# Sheet1.net
KiCad netlist of a schematic drawn in Altium Designer
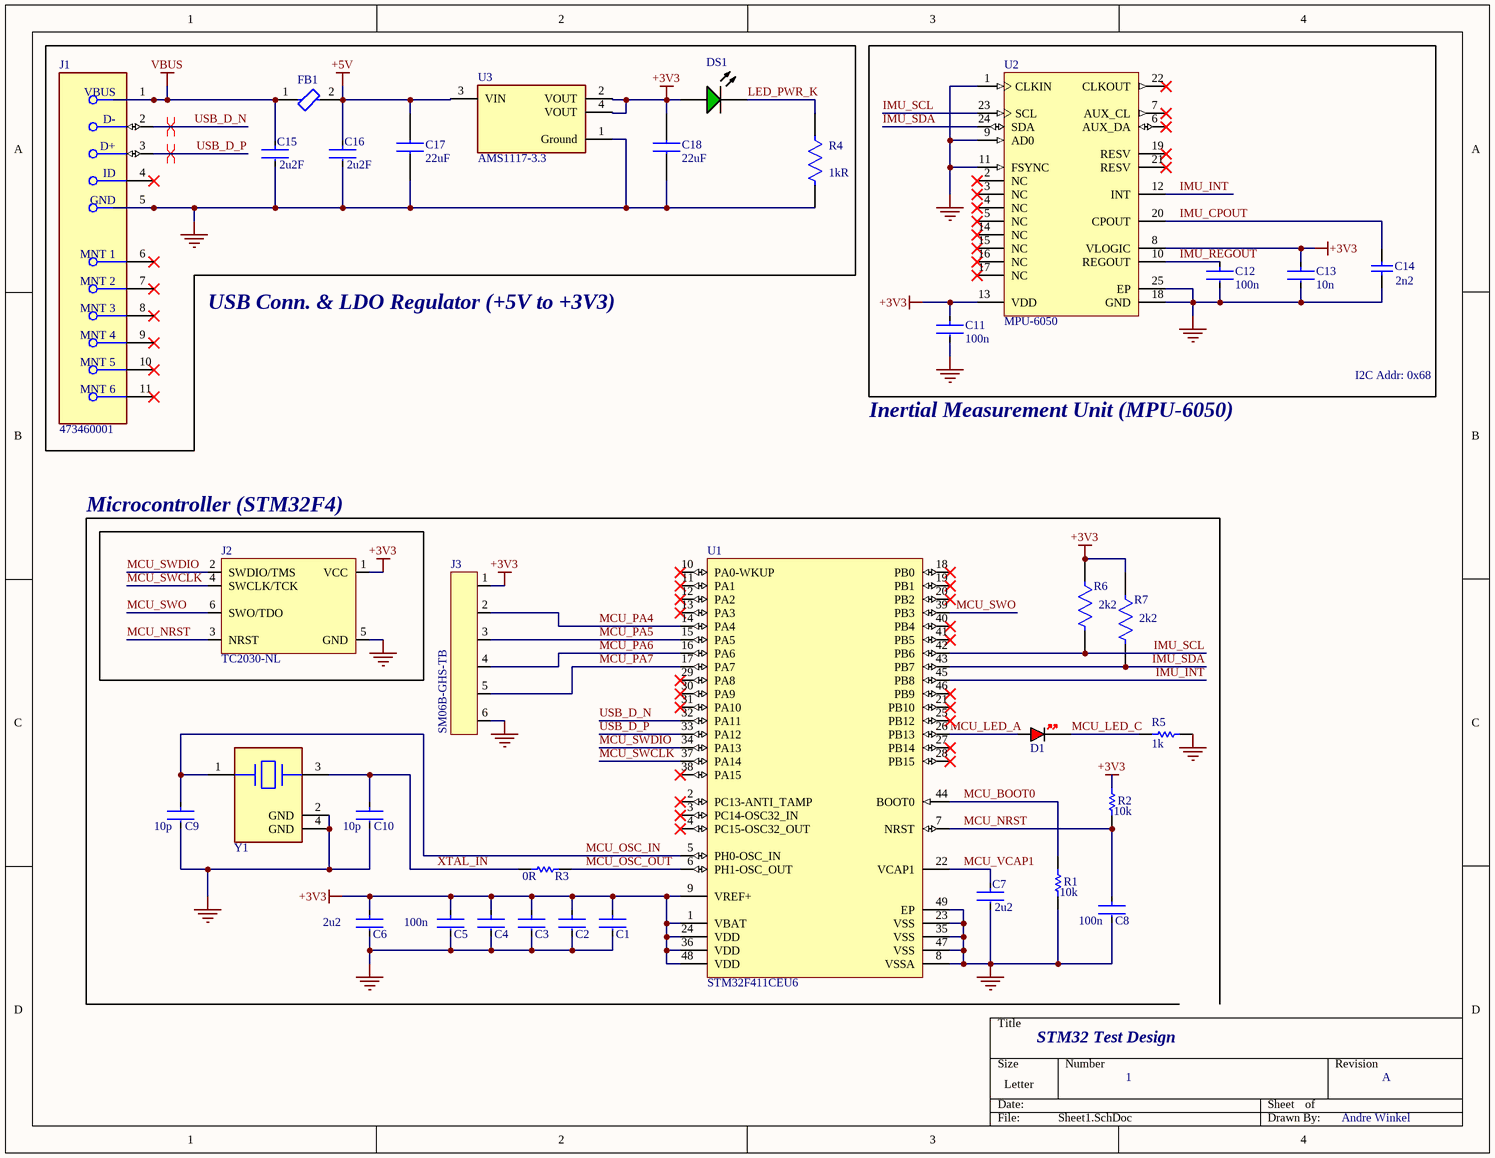
[diagram p0: Sheet1.SchDoc]

(export (version "E")
  (design (tool "Eeschema 10.0.6"))
  (components
    (comp (ref "C1")
      (value "GCM155R71C104KA55D")
      (footprint "FP-GCM155-0_05-IPC_C")
      (description "Ceramic Capacitor for Automotive 100nF ±10% 16VDC X7R 0402 Paper T/R")
      (fields (field (name "VOLTAGE") "16V") (field (name "TOLERANCE") "10%"))
      (libsource (lib "Altium Content Vault") (part "02cd4be3c70576c341d710602a673aa"))
    )
    (comp (ref "C2")
      (value "GCM155R71C104KA55D")
      (footprint "FP-GCM155-0_05-IPC_C")
      (description "Ceramic Capacitor for Automotive 100nF ±10% 16VDC X7R 0402 Paper T/R")
      (fields (field (name "VOLTAGE") "16V") (field (name "TOLERANCE") "10%"))
      (libsource (lib "Altium Content Vault") (part "02cd4be3c70576c341d710602a673aa"))
    )
    (comp (ref "C3")
      (value "GCM155R71C104KA55D")
      (footprint "FP-GCM155-0_05-IPC_C")
      (description "Ceramic Capacitor for Automotive 100nF ±10% 16VDC X7R 0402 Paper T/R")
      (fields (field (name "VOLTAGE") "16V") (field (name "TOLERANCE") "10%"))
      (libsource (lib "Altium Content Vault") (part "02cd4be3c70576c341d710602a673aa"))
    )
    (comp (ref "C4")
      (value "GCM155R71C104KA55D")
      (footprint "FP-GCM155-0_05-IPC_C")
      (description "Ceramic Capacitor for Automotive 100nF ±10% 16VDC X7R 0402 Paper T/R")
      (fields (field (name "VOLTAGE") "16V") (field (name "TOLERANCE") "10%"))
      (libsource (lib "Altium Content Vault") (part "02cd4be3c70576c341d710602a673aa"))
    )
    (comp (ref "C5")
      (value "GCM155R71C104KA55D")
      (footprint "FP-GCM155-0_05-IPC_C")
      (description "Ceramic Capacitor for Automotive 100nF ±10% 16VDC X7R 0402 Paper T/R")
      (fields
        (field (name "VOLTAGE") "16V")
        (field (name "TOLERANCE") "10%")
        (field (name "CAPACITANCE") "100n")
      )
      (libsource (lib "Altium Content Vault") (part "02cd4be3c70576c341d710602a673aa"))
    )
    (comp (ref "C6")
      (value "CGA3E1X7S1C225K080AE")
      (footprint "FP-CGA3E-0_3-0_1-IPC_C")
      (description "Cap Ceramic 2.2uF 16V X7S 10% Pad SMD 0603 +125°C Automotive T/R")
      (fields (field (name "TOLERANCE") "10%") (field (name "CAPACITANCE") "2u2"))
      (libsource (lib "Altium Content Vault") (part "b4654b650e69147ec39a6b967a45e02"))
    )
    (comp (ref "C7")
      (value "CGA3E1X7S1C225K080AE")
      (footprint "FP-CGA3E-0_3-0_1-IPC_C")
      (description "Cap Ceramic 2.2uF 16V X7S 10% Pad SMD 0603 +125°C Automotive T/R")
      (fields (field (name "TOLERANCE") "10%") (field (name "CAPACITANCE") "2u2"))
      (libsource (lib "Altium Content Vault") (part "b4654b650e69147ec39a6b967a45e02"))
    )
    (comp (ref "C8")
      (value "GCM155R71C104KA55D")
      (footprint "FP-GCM155-0_05-IPC_C")
      (description "Ceramic Capacitor for Automotive 100nF ±10% 16VDC X7R 0402 Paper T/R")
      (fields
        (field (name "VOLTAGE") "16V")
        (field (name "TOLERANCE") "10%")
        (field (name "CAPACITANCE") "100n")
      )
      (libsource (lib "Altium Content Vault") (part "02cd4be3c70576c341d710602a673aa"))
    )
    (comp (ref "C9")
      (value "GJM0335C1E100GB01D")
      (footprint "FP-GJM033-0_03-IPC_B")
      (description "Ceramic Capacitor 10pF ±2% 25V C0G 0201 (0603 Metric)")
      (fields (field (name "CAPACITANCE") "10p") (field (name "TOLERANCE") "2%"))
      (libsource (lib "Altium Content Vault") (part "b4654b650e69147ec39a6b967a45e02"))
    )
    (comp (ref "C10")
      (value "GJM0335C1E100GB01D")
      (footprint "FP-GJM033-0_03-IPC_B")
      (description "Ceramic Capacitor 10pF ±2% 25V C0G 0201 (0603 Metric)")
      (fields (field (name "CAPACITANCE") "10p") (field (name "TOLERANCE") "2%"))
      (libsource (lib "Altium Content Vault") (part "b4654b650e69147ec39a6b967a45e02"))
    )
    (comp (ref "C11")
      (value "GCM155R71C104KA55D")
      (footprint "FP-GCM155-0_05-IPC_C")
      (description "Ceramic Capacitor for Automotive 100nF ±10% 16VDC X7R 0402 Paper T/R")
      (fields
        (field (name "VOLTAGE") "16V")
        (field (name "TOLERANCE") "10%")
        (field (name "CAPACITANCE") "100n")
      )
      (libsource (lib "Altium Content Vault") (part "02cd4be3c70576c341d710602a673aa"))
    )
    (comp (ref "C12")
      (value "GCM155R71C104KA55D")
      (footprint "FP-GCM155-0_05-IPC_C")
      (description "Ceramic Capacitor for Automotive 100nF ±10% 16VDC X7R 0402 Paper T/R")
      (fields
        (field (name "VOLTAGE") "16V")
        (field (name "TOLERANCE") "10%")
        (field (name "CAPACITANCE") "100n")
      )
      (libsource (lib "Altium Content Vault") (part "02cd4be3c70576c341d710602a673aa"))
    )
    (comp (ref "C13")
      (value "C0603X7R0J103K030BA")
      (footprint "FP-C0603-030-0_03-IPC_B")
      (description "Multilayer Ceramic Capacitors 10nF ±10% 6.3V X7R SMD 0201")
      (fields (field (name "CAPACITANCE") "10n") (field (name "TOLERANCE") "10%"))
      (libsource (lib "Altium Content Vault") (part "02cd4be3c70576c341d710602a673aa"))
    )
    (comp (ref "C14")
      (value "2n2")
      (footprint "CAPC1608X87X35NL15T15")
      (fields (field (name "MANUFACTURER") "Kemet") (field (name "PART NUMBER") "C0603X222K5RACTU"))
      (libsource (lib "Altium Content Vault") (part "CAP"))
    )
    (comp (ref "C15")
      (value "CGA3E1X7S1C225K080AE")
      (footprint "FP-CGA3E-0_3-0_1-IPC_C")
      (description "Cap Ceramic 2.2uF 16V X7S 10% Pad SMD 0603 +125°C Automotive T/R")
      (fields (field (name "TOLERANCE") "10%") (field (name "CAPACITANCE") "2u2F"))
      (libsource (lib "Altium Content Vault") (part "b4654b650e69147ec39a6b967a45e02"))
    )
    (comp (ref "C16")
      (value "CGA3E1X7S1C225K080AE")
      (footprint "FP-CGA3E-0_3-0_1-IPC_C")
      (description "Cap Ceramic 2.2uF 16V X7S 10% Pad SMD 0603 +125°C Automotive T/R")
      (fields (field (name "TOLERANCE") "10%") (field (name "CAPACITANCE") "2u2F"))
      (libsource (lib "Altium Content Vault") (part "b4654b650e69147ec39a6b967a45e02"))
    )
    (comp (ref "C17")
      (value "C2012X5R1C226M085AC")
      (footprint "SamacSys:C2012_Commercial")
      (description "Capacitor")
      (fields (field (name "MOUSER PART NUMBER") "810-C2012X5R1C226MAC") (field (name "CAPACITANCE") "22uF"))
      (libsource (lib "*") (part "C2012X5R1C226M085AC"))
    )
    (comp (ref "C18")
      (value "C2012X5R1C226M085AC")
      (footprint "SamacSys:C2012_Commercial")
      (description "Capacitor")
      (fields (field (name "MOUSER PART NUMBER") "810-C2012X5R1C226MAC") (field (name "CAPACITANCE") "22uF"))
      (libsource (lib "*") (part "C2012X5R1C226M085AC"))
    )
    (comp (ref "D1")
      (value "RED")
      (footprint "LED_0402_RED")
      (description "LED 0402 RED SMD")
      (libsource (lib "Schematic-Lib-PhilsLab") (part "LED_0402_RED"))
    )
    (comp (ref "DS1")
      (value "HSMG-C170")
      (footprint "AVAG-HSMX-C170_V")
      (description "Chip LED, Green, 2.2 V, -40 to 85 degC, 2-Pin SMD, Pb-Free, Tape and Reel")
      (fields (field (name "MANUFACTURER") "Avago"))
      (libsource (lib "Altium Content Vault") (part "LED_GREEN_A1K2-2"))
    )
    (comp (ref "FB1")
      (value "BLM31PG121SN1L")
      (footprint "FP-BLM31-0_2-t1_1-MFG")
      (description "Chip Ferrite Bead Array, 1206, 120Ω @ 100MHz, 0.02Ω, 25%, 3.5A")
      (fields (field (name "TOLERANCE") "25%"))
      (libsource (lib "Altium Content Vault") (part "5f30dd21d616792df468990f7003faa"))
    )
    (comp (ref "J1")
      (value "473460001")
      (footprint "FP-473460001-MFG")
      (description "CONN RCPT USB2.0 MICRO B SMD R/A")
      (fields
        (field (name "OCTOPART") "https://octopart.com/47346-0001-molex-7164928")
        (field (name "MANUFACTURER") "Molex")
      )
      (libsource (lib "Altium Content Vault") (part "53ae1f1d9b557310b43ca686e5bb76a"))
    )
    (comp (ref "J2")
      (value "TC2030-NL")
      (footprint "TC2030-NL-FP")
      (description "Tag-Connect No-Solder SWD Debug Connector (No Legs) DO NOT PLACE")
      (fields
        (field (name "MANUFACTURER") "Tag-Connect")
        (field (name "MANUFACTURER PART NUMBER") "TC2030-NL-FP")
      )
      (libsource (lib "Schematic-Lib-PhilsLab") (part "TC2030-NL"))
    )
    (comp (ref "J3")
      (value "SM06B-GHS-TB")
      (footprint "SM06B-GHS-TB")
      (description "Header Connector 6 Position 1.25MM Pitch SMD Horizontal JST GH")
      (fields (field (name "MANUFACTURER") "JST"))
      (libsource (lib "Schematic-Lib-PhilsLab") (part "SM06B-GHS-TB"))
    )
    (comp (ref "R1")
      (value "CRG0201F10K")
      (footprint "RESC0603X26X15LL03T05")
      (fields (field (name "MANUFACTURER") "TE Connectivity / AMP") (field (name "RESISTANCE") "10k"))
      (libsource (lib "Altium Content Vault") (part "RES"))
    )
    (comp (ref "R2")
      (value "CRG0201F10K")
      (footprint "RESC0603X26X15LL03T05")
      (fields (field (name "MANUFACTURER") "TE Connectivity / AMP") (field (name "RESISTANCE") "10k"))
      (libsource (lib "Altium Content Vault") (part "RES"))
    )
    (comp (ref "R3")
      (value "ERJ2GE0R00X")
      (footprint "RESC1005X40X25LL05T05")
      (description "Chip Resistor, 0 Ohm, 0.1 W, -55 to 155 degC, 0402 (1005 Metric), RoHS, Tape and Reel")
      (fields
        (field (name "MANUFACTURER") "Panasonic")
        (field (name "RESISTANCE") "0R")
        (field (name "TOLERANCE") "5%")
      )
      (libsource (lib "Altium Content Vault") (part "RES-2"))
    )
    (comp (ref "R4")
      (value "AC0603FR-071KL")
      (footprint "FP-AC0603-IPC_B")
      (description "RES 1kΩ 1.00% 0.1W 0603")
      (fields (field (name "TOLERANCE") "1%") (field (name "RESISTANCE") "1kR"))
      (libsource (lib "Altium Content Vault") (part "1029c3af85768c4190bb7ad29bc67b5"))
    )
    (comp (ref "R5")
      (value "CRG0201F10K")
      (footprint "RESC0603X26X15LL03T05")
      (fields (field (name "MANUFACTURER") "TE Connectivity / AMP") (field (name "RESISTANCE") "1k"))
      (libsource (lib "Altium Content Vault") (part "RES"))
    )
    (comp (ref "R6")
      (value "2k2")
      (footprint "FP-CRGCQ0402-IPC_C")
      (description "CRGCQ0402 2.2KΩ 5% ±100ppm/°C 50V")
      (fields
        (field (name "MANUFACTURER") "TE Connectivity")
        (field (name "MANUFACTURER PART NUMBER") "CRGCQ0402J2K2")
      )
      (libsource (lib "Altium Content Vault") (part "1029c3af85768c4190bb7ad29bc67b5"))
    )
    (comp (ref "R7")
      (value "2k2")
      (footprint "FP-CRGCQ0402-IPC_C")
      (description "CRGCQ0402 2.2KΩ 5% ±100ppm/°C 50V")
      (fields
        (field (name "MANUFACTURER") "TE Connectivity")
        (field (name "MANUFACTURER PART NUMBER") "CRGCQ0402J2K2")
      )
      (libsource (lib "Altium Content Vault") (part "1029c3af85768c4190bb7ad29bc67b5"))
    )
    (comp (ref "U1")
      (value "STM32F411CEU6")
      (footprint "STM-UFQFPN48_L")
      (libsource (lib "Altium Content Vault") (part "MC-ARM-STM32F411-UFQFPN48"))
    )
    (comp (ref "U2")
      (value "MPU-6050")
      (footprint "IS-QFN-24_V")
      (fields (field (name "MANUFACTURER") "InvenSense"))
      (libsource (lib "Altium Content Vault") (part "IS-MPU-6050-QFN-24"))
    )
    (comp (ref "U3")
      (value "AMS1117-3.3")
      (footprint "FP-AMS1117-IPC_C")
      (description "LDO Voltage Regulators 1A, 3.3V")
      (fields
        (field (name "OCTOPART") "https://octopart.com/ams1117-3.3-advanced+monolithic+systems-25899300")
        (field (name "MANUFACTURER") "Advanced Monolithic Systems")
      )
      (libsource (lib "Altium Content Vault") (part "8bdbb5f8e77002000e30dd2845d0354"))
    )
    (comp (ref "Y1")
      (value "ABM10AIG-24.000MHZ-2Z-T")
      (footprint "FP-ABM10AIG-MFG")
      (description "Crystal 24MHz ±20ppm 10pF SMD-4 2.5mm x 2mm Automotive")
      (libsource (lib "Altium Content Vault") (part "40c3c19da1ce8e2d75e34138d1085e7"))
    )
  )
  (nets
    (net (code "1") (name "+3V3") (class "Default")
      (node (ref "C1") (pin "1") (pinfunction "1_1") (pintype "passive"))
      (node (ref "C11") (pin "1") (pinfunction "1_1") (pintype "passive"))
      (node (ref "C13") (pin "1") (pinfunction "1_1") (pintype "passive"))
      (node (ref "C18") (pin "1") (pinfunction "1_1") (pintype "passive"))
      (node (ref "C2") (pin "1") (pinfunction "1_1") (pintype "passive"))
      (node (ref "C3") (pin "1") (pinfunction "1_1") (pintype "passive"))
      (node (ref "C4") (pin "1") (pinfunction "1_1") (pintype "passive"))
      (node (ref "C5") (pin "1") (pinfunction "1_1") (pintype "passive"))
      (node (ref "C6") (pin "1") (pinfunction "1_1") (pintype "passive"))
      (node (ref "DS1") (pin "1") (pinfunction "A_1") (pintype "passive"))
      (node (ref "J2") (pin "1") (pinfunction "VCC_1") (pintype "passive"))
      (node (ref "J3") (pin "1") (pinfunction "1_1") (pintype "passive"))
      (node (ref "R2") (pin "2") (pinfunction "2_2") (pintype "passive"))
      (node (ref "R6") (pin "1") (pinfunction "1_1") (pintype "passive"))
      (node (ref "R7") (pin "1") (pinfunction "1_1") (pintype "passive"))
      (node (ref "U1") (pin "1") (pinfunction "VBAT_1") (pintype "power_in"))
      (node (ref "U1") (pin "24") (pinfunction "VDD_24") (pintype "power_in"))
      (node (ref "U1") (pin "36") (pinfunction "VDD_36") (pintype "power_in"))
      (node (ref "U1") (pin "48") (pinfunction "VDD_48") (pintype "power_in"))
      (node (ref "U1") (pin "9") (pinfunction "VREF+_9") (pintype "power_in"))
      (node (ref "U2") (pin "13") (pinfunction "VDD_13") (pintype "power_in"))
      (node (ref "U2") (pin "8") (pinfunction "VLOGIC_8") (pintype "power_in"))
      (node (ref "U3") (pin "2") (pinfunction "VOUT_2") (pintype "passive"))
      (node (ref "U3") (pin "4") (pinfunction "VOUT_4") (pintype "passive"))
    )
    (net (code "2") (name "+5V") (class "Default")
      (node (ref "C16") (pin "1") (pinfunction "1_1") (pintype "passive"))
      (node (ref "C17") (pin "1") (pinfunction "1_1") (pintype "passive"))
      (node (ref "FB1") (pin "2") (pinfunction "2_2") (pintype "passive"))
      (node (ref "U3") (pin "3") (pinfunction "VIN_3") (pintype "power_in"))
    )
    (net (code "3") (name "/IMU_CPOUT") (class "Default")
      (node (ref "C14") (pin "1") (pinfunction "1_1") (pintype "passive"))
      (node (ref "U2") (pin "20") (pinfunction "CPOUT_20") (pintype "passive"))
    )
    (net (code "4") (name "/IMU_INT") (class "Default")
      (node (ref "U1") (pin "45") (pinfunction "PB8_45") (pintype "bidirectional"))
      (node (ref "U2") (pin "12") (pinfunction "INT_12") (pintype "open_collector"))
    )
    (net (code "5") (name "/IMU_REGOUT") (class "Default")
      (node (ref "C12") (pin "1") (pinfunction "1_1") (pintype "passive"))
      (node (ref "U2") (pin "10") (pinfunction "REGOUT_10") (pintype "passive"))
    )
    (net (code "6") (name "/IMU_SCL") (class "Default")
      (node (ref "R6") (pin "2") (pinfunction "2_2") (pintype "passive"))
      (node (ref "U1") (pin "42") (pinfunction "PB6_42") (pintype "bidirectional"))
      (node (ref "U2") (pin "23") (pinfunction "SCL_23") (pintype "input"))
    )
    (net (code "7") (name "/IMU_SDA") (class "Default")
      (node (ref "R7") (pin "2") (pinfunction "2_2") (pintype "passive"))
      (node (ref "U1") (pin "43") (pinfunction "PB7_43") (pintype "bidirectional"))
      (node (ref "U2") (pin "24") (pinfunction "SDA_24") (pintype "bidirectional"))
    )
    (net (code "8") (name "/LED_PWR_K") (class "Default")
      (node (ref "DS1") (pin "2") (pinfunction "K_2") (pintype "passive"))
      (node (ref "R4") (pin "1") (pinfunction "1_1") (pintype "passive"))
    )
    (net (code "9") (name "/MCU_BOOT0") (class "Default")
      (node (ref "R1") (pin "2") (pinfunction "2_2") (pintype "passive"))
      (node (ref "U1") (pin "44") (pinfunction "BOOT0_44") (pintype "input"))
    )
    (net (code "10") (name "/MCU_LED_A") (class "Default")
      (node (ref "D1") (pin "A") (pinfunction "A_A") (pintype "passive"))
      (node (ref "U1") (pin "26") (pinfunction "PB13_26") (pintype "bidirectional"))
    )
    (net (code "11") (name "/MCU_LED_C") (class "Default")
      (node (ref "D1") (pin "K") (pinfunction "K_K") (pintype "passive"))
      (node (ref "R5") (pin "2") (pinfunction "2_2") (pintype "passive"))
    )
    (net (code "12") (name "/MCU_NRST") (class "Default")
      (node (ref "C8") (pin "1") (pinfunction "1_1") (pintype "passive"))
      (node (ref "J2") (pin "3") (pinfunction "NRST_3") (pintype "passive"))
      (node (ref "R2") (pin "1") (pinfunction "1_1") (pintype "passive"))
      (node (ref "U1") (pin "7") (pinfunction "NRST_7") (pintype "bidirectional"))
    )
    (net (code "13") (name "/MCU_OSC_IN") (class "Default")
      (node (ref "C9") (pin "1") (pinfunction "1_1") (pintype "passive"))
      (node (ref "U1") (pin "5") (pinfunction "PH0-OSC_IN_5") (pintype "bidirectional"))
      (node (ref "Y1") (pin "1") (pinfunction "1_Crystal_1") (pintype "passive"))
    )
    (net (code "14") (name "/MCU_OSC_OUT") (class "Default")
      (node (ref "R3") (pin "2") (pinfunction "2_2") (pintype "passive"))
      (node (ref "U1") (pin "6") (pinfunction "PH1-OSC_OUT_6") (pintype "bidirectional"))
    )
    (net (code "15") (name "/MCU_PA4") (class "Default")
      (node (ref "J3") (pin "2") (pinfunction "2_2") (pintype "passive"))
      (node (ref "U1") (pin "14") (pinfunction "PA4_14") (pintype "bidirectional"))
    )
    (net (code "16") (name "/MCU_PA5") (class "Default")
      (node (ref "J3") (pin "3") (pinfunction "3_3") (pintype "passive"))
      (node (ref "U1") (pin "15") (pinfunction "PA5_15") (pintype "bidirectional"))
    )
    (net (code "17") (name "/MCU_PA6") (class "Default")
      (node (ref "J3") (pin "4") (pinfunction "4_4") (pintype "passive"))
      (node (ref "U1") (pin "16") (pinfunction "PA6_16") (pintype "bidirectional"))
    )
    (net (code "18") (name "/MCU_PA7") (class "Default")
      (node (ref "J3") (pin "5") (pinfunction "5_5") (pintype "passive"))
      (node (ref "U1") (pin "17") (pinfunction "PA7_17") (pintype "bidirectional"))
    )
    (net (code "19") (name "/MCU_SWCLK") (class "Default")
      (node (ref "J2") (pin "4") (pinfunction "SWCLK/TCK_4") (pintype "passive"))
      (node (ref "U1") (pin "37") (pinfunction "PA14_37") (pintype "bidirectional"))
    )
    (net (code "20") (name "/MCU_SWDIO") (class "Default")
      (node (ref "J2") (pin "2") (pinfunction "SWDIO/TMS_2") (pintype "passive"))
      (node (ref "U1") (pin "34") (pinfunction "PA13_34") (pintype "bidirectional"))
    )
    (net (code "21") (name "/MCU_SWO") (class "Default")
      (node (ref "J2") (pin "6") (pinfunction "SWO/TDO_6") (pintype "passive"))
      (node (ref "U1") (pin "39") (pinfunction "PB3_39") (pintype "bidirectional"))
    )
    (net (code "22") (name "/MCU_VCAP1") (class "Default")
      (node (ref "C7") (pin "1") (pinfunction "1_1") (pintype "passive"))
      (node (ref "U1") (pin "22") (pinfunction "VCAP1_22") (pintype "passive"))
    )
    (net (code "23") (name "/USB_D_N") (class "Default")
      (node (ref "J1") (pin "2") (pinfunction "D-_2") (pintype "bidirectional"))
      (node (ref "U1") (pin "32") (pinfunction "PA11_32") (pintype "bidirectional"))
    )
    (net (code "24") (name "/USB_D_P") (class "Default")
      (node (ref "J1") (pin "3") (pinfunction "D+_3") (pintype "bidirectional"))
      (node (ref "U1") (pin "33") (pinfunction "PA12_33") (pintype "bidirectional"))
    )
    (net (code "25") (name "/XTAL_IN") (class "Default")
      (node (ref "C10") (pin "1") (pinfunction "1_1") (pintype "passive"))
      (node (ref "R3") (pin "1") (pinfunction "1_1") (pintype "passive"))
      (node (ref "Y1") (pin "3") (pinfunction "2_Crystal_3") (pintype "passive"))
    )
    (net (code "26") (name "GND") (class "Default")
      (node (ref "C1") (pin "2") (pinfunction "2_2") (pintype "passive"))
      (node (ref "C10") (pin "2") (pinfunction "2_2") (pintype "passive"))
      (node (ref "C11") (pin "2") (pinfunction "2_2") (pintype "passive"))
      (node (ref "C12") (pin "2") (pinfunction "2_2") (pintype "passive"))
      (node (ref "C13") (pin "2") (pinfunction "2_2") (pintype "passive"))
      (node (ref "C14") (pin "2") (pinfunction "2_2") (pintype "passive"))
      (node (ref "C15") (pin "2") (pinfunction "2_2") (pintype "passive"))
      (node (ref "C16") (pin "2") (pinfunction "2_2") (pintype "passive"))
      (node (ref "C17") (pin "2") (pinfunction "2_2") (pintype "passive"))
      (node (ref "C18") (pin "2") (pinfunction "2_2") (pintype "passive"))
      (node (ref "C2") (pin "2") (pinfunction "2_2") (pintype "passive"))
      (node (ref "C3") (pin "2") (pinfunction "2_2") (pintype "passive"))
      (node (ref "C4") (pin "2") (pinfunction "2_2") (pintype "passive"))
      (node (ref "C5") (pin "2") (pinfunction "2_2") (pintype "passive"))
      (node (ref "C6") (pin "2") (pinfunction "2_2") (pintype "passive"))
      (node (ref "C7") (pin "2") (pinfunction "2_2") (pintype "passive"))
      (node (ref "C8") (pin "2") (pinfunction "2_2") (pintype "passive"))
      (node (ref "C9") (pin "2") (pinfunction "2_2") (pintype "passive"))
      (node (ref "J1") (pin "5") (pinfunction "GND_5") (pintype "power_in"))
      (node (ref "J2") (pin "5") (pinfunction "GND_5") (pintype "passive"))
      (node (ref "J3") (pin "6") (pinfunction "6_6") (pintype "passive"))
      (node (ref "R1") (pin "1") (pinfunction "1_1") (pintype "passive"))
      (node (ref "R4") (pin "2") (pinfunction "2_2") (pintype "passive"))
      (node (ref "R5") (pin "1") (pinfunction "1_1") (pintype "passive"))
      (node (ref "U1") (pin "23") (pinfunction "VSS_23") (pintype "power_in"))
      (node (ref "U1") (pin "35") (pinfunction "VSS_35") (pintype "power_in"))
      (node (ref "U1") (pin "47") (pinfunction "VSS_47") (pintype "power_in"))
      (node (ref "U1") (pin "49") (pinfunction "EP_49") (pintype "power_in"))
      (node (ref "U1") (pin "8") (pinfunction "VSSA_8") (pintype "power_in"))
      (node (ref "U2") (pin "1") (pinfunction "CLKIN_1") (pintype "input"))
      (node (ref "U2") (pin "11") (pinfunction "FSYNC_11") (pintype "input"))
      (node (ref "U2") (pin "18") (pinfunction "GND_18") (pintype "power_in"))
      (node (ref "U2") (pin "25") (pinfunction "EP_25") (pintype "power_in"))
      (node (ref "U2") (pin "9") (pinfunction "AD0_9") (pintype "input"))
      (node (ref "U3") (pin "1") (pinfunction "Ground_1") (pintype "power_in"))
      (node (ref "Y1") (pin "2") (pinfunction "GND_2") (pintype "power_in"))
      (node (ref "Y1") (pin "4") (pinfunction "GND_4") (pintype "power_in"))
    )
    (net (code "27") (name "VBUS") (class "Default")
      (node (ref "C15") (pin "1") (pinfunction "1_1") (pintype "passive"))
      (node (ref "FB1") (pin "1") (pinfunction "1_1") (pintype "passive"))
      (node (ref "J1") (pin "1") (pinfunction "VBUS_1") (pintype "power_in"))
    )
    (net (code "28") (name "unconnected-(J1-ID-Pad4)") (class "Default")
      (node (ref "J1") (pin "4") (pinfunction "ID_4") (pintype "passive+no_connect"))
    )
    (net (code "29") (name "unconnected-(J1-MNT_1-Pad6)") (class "Default")
      (node (ref "J1") (pin "6") (pinfunction "MNT_1_6") (pintype "passive+no_connect"))
    )
    (net (code "30") (name "unconnected-(J1-MNT_2-Pad7)") (class "Default")
      (node (ref "J1") (pin "7") (pinfunction "MNT_2_7") (pintype "passive+no_connect"))
    )
    (net (code "31") (name "unconnected-(J1-MNT_3-Pad8)") (class "Default")
      (node (ref "J1") (pin "8") (pinfunction "MNT_3_8") (pintype "passive+no_connect"))
    )
    (net (code "32") (name "unconnected-(J1-MNT_4-Pad9)") (class "Default")
      (node (ref "J1") (pin "9") (pinfunction "MNT_4_9") (pintype "passive+no_connect"))
    )
    (net (code "33") (name "unconnected-(J1-MNT_5-Pad10)") (class "Default")
      (node (ref "J1") (pin "10") (pinfunction "MNT_5_10") (pintype "passive+no_connect"))
    )
    (net (code "34") (name "unconnected-(J1-MNT_6-Pad11)") (class "Default")
      (node (ref "J1") (pin "11") (pinfunction "MNT_6_11") (pintype "passive+no_connect"))
    )
    (net (code "35") (name "unconnected-(U1-PA0-WKUP-Pad10)") (class "Default")
      (node (ref "U1") (pin "10") (pinfunction "PA0-WKUP_10") (pintype "bidirectional+no_connect"))
    )
    (net (code "36") (name "unconnected-(U1-PA1-Pad11)") (class "Default")
      (node (ref "U1") (pin "11") (pinfunction "PA1_11") (pintype "bidirectional+no_connect"))
    )
    (net (code "37") (name "unconnected-(U1-PA2-Pad12)") (class "Default")
      (node (ref "U1") (pin "12") (pinfunction "PA2_12") (pintype "bidirectional+no_connect"))
    )
    (net (code "38") (name "unconnected-(U1-PA3-Pad13)") (class "Default")
      (node (ref "U1") (pin "13") (pinfunction "PA3_13") (pintype "bidirectional+no_connect"))
    )
    (net (code "39") (name "unconnected-(U1-PA8-Pad29)") (class "Default")
      (node (ref "U1") (pin "29") (pinfunction "PA8_29") (pintype "bidirectional+no_connect"))
    )
    (net (code "40") (name "unconnected-(U1-PA9-Pad30)") (class "Default")
      (node (ref "U1") (pin "30") (pinfunction "PA9_30") (pintype "bidirectional+no_connect"))
    )
    (net (code "41") (name "unconnected-(U1-PA10-Pad31)") (class "Default")
      (node (ref "U1") (pin "31") (pinfunction "PA10_31") (pintype "bidirectional+no_connect"))
    )
    (net (code "42") (name "unconnected-(U1-PA15-Pad38)") (class "Default")
      (node (ref "U1") (pin "38") (pinfunction "PA15_38") (pintype "bidirectional+no_connect"))
    )
    (net (code "43") (name "unconnected-(U1-PB0-Pad18)") (class "Default")
      (node (ref "U1") (pin "18") (pinfunction "PB0_18") (pintype "bidirectional+no_connect"))
    )
    (net (code "44") (name "unconnected-(U1-PB1-Pad19)") (class "Default")
      (node (ref "U1") (pin "19") (pinfunction "PB1_19") (pintype "bidirectional+no_connect"))
    )
    (net (code "45") (name "unconnected-(U1-PB2-Pad20)") (class "Default")
      (node (ref "U1") (pin "20") (pinfunction "PB2_20") (pintype "bidirectional+no_connect"))
    )
    (net (code "46") (name "unconnected-(U1-PB4-Pad40)") (class "Default")
      (node (ref "U1") (pin "40") (pinfunction "PB4_40") (pintype "bidirectional+no_connect"))
    )
    (net (code "47") (name "unconnected-(U1-PB5-Pad41)") (class "Default")
      (node (ref "U1") (pin "41") (pinfunction "PB5_41") (pintype "bidirectional+no_connect"))
    )
    (net (code "48") (name "unconnected-(U1-PB9-Pad46)") (class "Default")
      (node (ref "U1") (pin "46") (pinfunction "PB9_46") (pintype "bidirectional+no_connect"))
    )
    (net (code "49") (name "unconnected-(U1-PB10-Pad21)") (class "Default")
      (node (ref "U1") (pin "21") (pinfunction "PB10_21") (pintype "bidirectional+no_connect"))
    )
    (net (code "50") (name "unconnected-(U1-PB12-Pad25)") (class "Default")
      (node (ref "U1") (pin "25") (pinfunction "PB12_25") (pintype "bidirectional+no_connect"))
    )
    (net (code "51") (name "unconnected-(U1-PB14-Pad27)") (class "Default")
      (node (ref "U1") (pin "27") (pinfunction "PB14_27") (pintype "bidirectional+no_connect"))
    )
    (net (code "52") (name "unconnected-(U1-PB15-Pad28)") (class "Default")
      (node (ref "U1") (pin "28") (pinfunction "PB15_28") (pintype "bidirectional+no_connect"))
    )
    (net (code "53") (name "unconnected-(U1-PC13-ANTI_TAMP-Pad2)") (class "Default")
      (node (ref "U1") (pin "2") (pinfunction "PC13-ANTI_TAMP_2") (pintype "bidirectional+no_connect"))
    )
    (net (code "54") (name "unconnected-(U1-PC14-OSC32_IN-Pad3)") (class "Default")
      (node (ref "U1") (pin "3") (pinfunction "PC14-OSC32_IN_3") (pintype "bidirectional+no_connect"))
    )
    (net (code "55") (name "unconnected-(U1-PC15-OSC32_OUT-Pad4)") (class "Default")
      (node (ref "U1") (pin "4") (pinfunction "PC15-OSC32_OUT_4") (pintype "bidirectional+no_connect"))
    )
    (net (code "56") (name "unconnected-(U2-AUX_CL-Pad7)") (class "Default")
      (node (ref "U2") (pin "7") (pinfunction "AUX_CL_7") (pintype "output+no_connect"))
    )
    (net (code "57") (name "unconnected-(U2-AUX_DA-Pad6)") (class "Default")
      (node (ref "U2") (pin "6") (pinfunction "AUX_DA_6") (pintype "bidirectional+no_connect"))
    )
    (net (code "58") (name "unconnected-(U2-CLKOUT-Pad22)") (class "Default")
      (node (ref "U2") (pin "22") (pinfunction "CLKOUT_22") (pintype "output+no_connect"))
    )
    (net (code "59") (name "unconnected-(U2-NC-Pad2)") (class "Default")
      (node (ref "U2") (pin "2") (pinfunction "NC_2") (pintype "passive+no_connect"))
    )
    (net (code "60") (name "unconnected-(U2-NC-Pad3)") (class "Default")
      (node (ref "U2") (pin "3") (pinfunction "NC_3") (pintype "passive+no_connect"))
    )
    (net (code "61") (name "unconnected-(U2-NC-Pad4)") (class "Default")
      (node (ref "U2") (pin "4") (pinfunction "NC_4") (pintype "passive+no_connect"))
    )
    (net (code "62") (name "unconnected-(U2-NC-Pad5)") (class "Default")
      (node (ref "U2") (pin "5") (pinfunction "NC_5") (pintype "passive+no_connect"))
    )
    (net (code "63") (name "unconnected-(U2-NC-Pad14)") (class "Default")
      (node (ref "U2") (pin "14") (pinfunction "NC_14") (pintype "passive+no_connect"))
    )
    (net (code "64") (name "unconnected-(U2-NC-Pad15)") (class "Default")
      (node (ref "U2") (pin "15") (pinfunction "NC_15") (pintype "passive+no_connect"))
    )
    (net (code "65") (name "unconnected-(U2-NC-Pad16)") (class "Default")
      (node (ref "U2") (pin "16") (pinfunction "NC_16") (pintype "passive+no_connect"))
    )
    (net (code "66") (name "unconnected-(U2-NC-Pad17)") (class "Default")
      (node (ref "U2") (pin "17") (pinfunction "NC_17") (pintype "passive+no_connect"))
    )
    (net (code "67") (name "unconnected-(U2-RESV-Pad19)") (class "Default")
      (node (ref "U2") (pin "19") (pinfunction "RESV_19") (pintype "passive+no_connect"))
    )
    (net (code "68") (name "unconnected-(U2-RESV-Pad21)") (class "Default")
      (node (ref "U2") (pin "21") (pinfunction "RESV_21") (pintype "passive+no_connect"))
    )
  )
)
